# Misc.net
KiCad netlist of a schematic drawn in Altium Designer
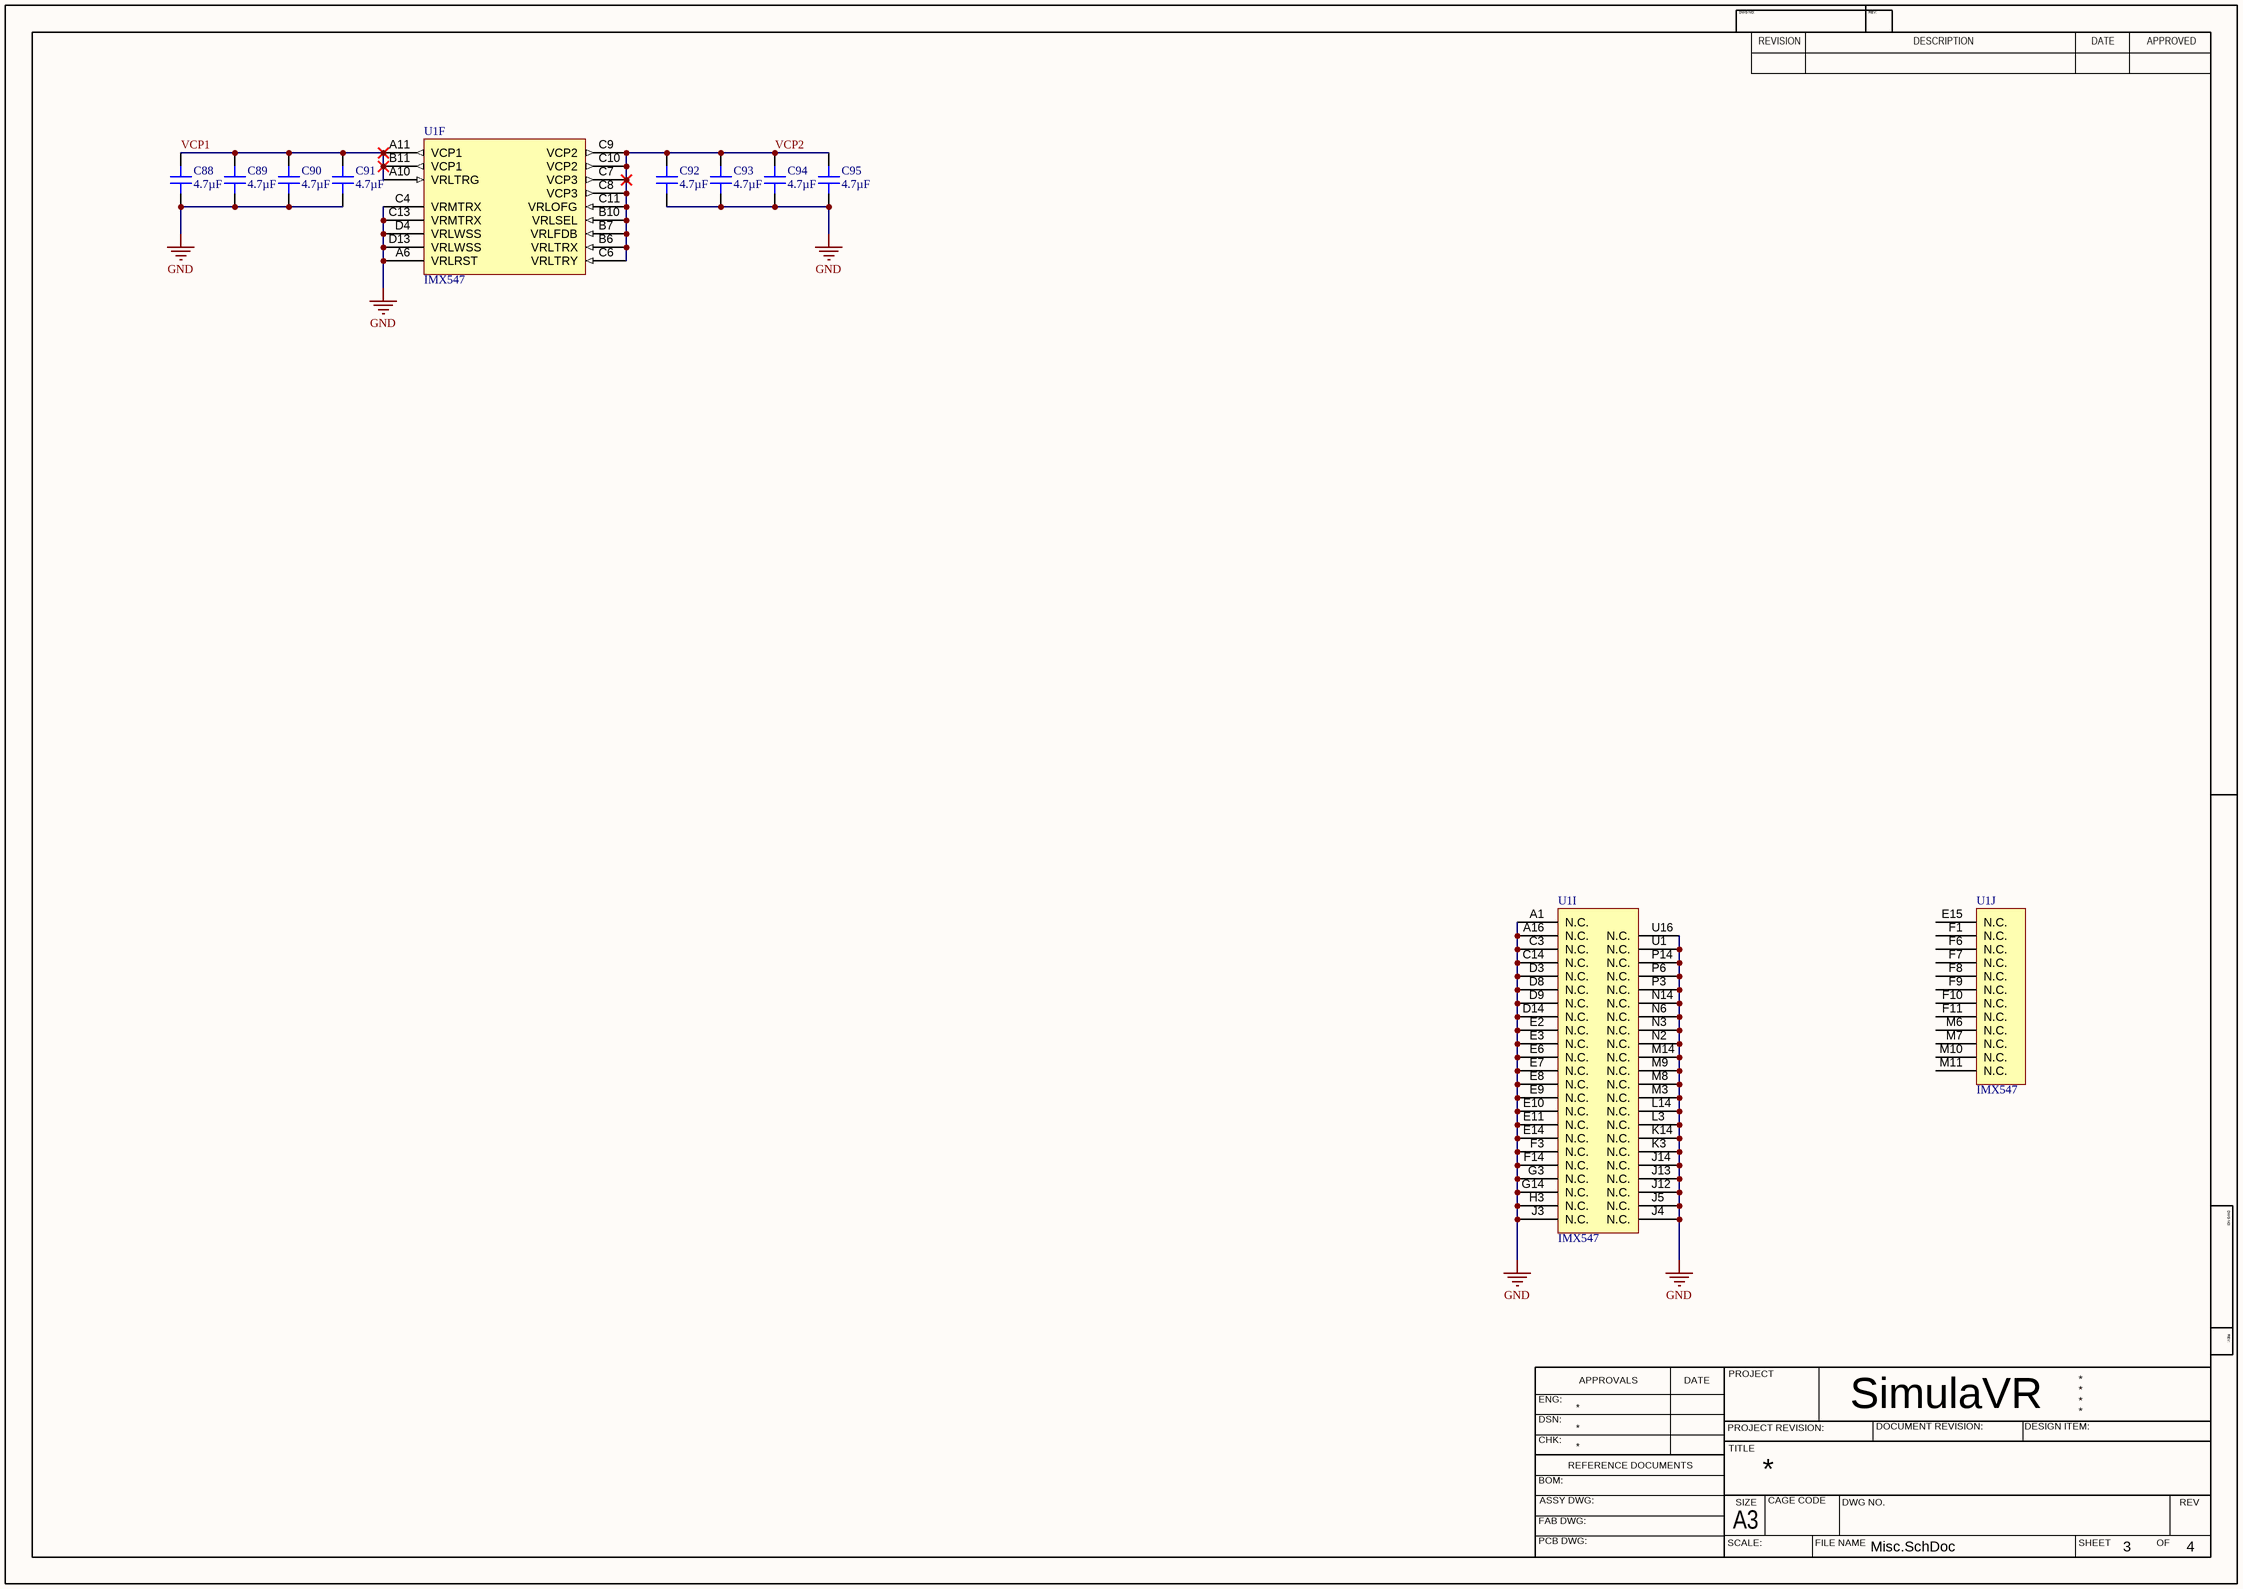
[diagram p0: Misc.SchDoc]

(export (version "E")
  (design (tool "Eeschema 10.0.6"))
  (components
    (comp (ref "C88")
      (value "4.7µF")
      (footprint "FP-GRM155-0_15-MFG")
      (description "CAP CER 4.7UF 10V X5R 0402")
      (fields
        (field (name "PART NUMBER") "GRM155R61A475MEAAD")
        (field (name "MANUFACTURER") "Murata Electronics")
      )
      (libsource (lib "Celestial Altium Library - altium_library") (part "Capacitor"))
    )
    (comp (ref "C89")
      (value "4.7µF")
      (footprint "FP-GRM155-0_15-MFG")
      (description "CAP CER 4.7UF 10V X5R 0402")
      (fields
        (field (name "PART NUMBER") "GRM155R61A475MEAAD")
        (field (name "MANUFACTURER") "Murata Electronics")
      )
      (libsource (lib "Celestial Altium Library - altium_library") (part "Capacitor"))
    )
    (comp (ref "C90")
      (value "4.7µF")
      (footprint "FP-GRM155-0_15-MFG")
      (description "CAP CER 4.7UF 10V X5R 0402")
      (fields
        (field (name "PART NUMBER") "GRM155R61A475MEAAD")
        (field (name "MANUFACTURER") "Murata Electronics")
      )
      (libsource (lib "Celestial Altium Library - altium_library") (part "Capacitor"))
    )
    (comp (ref "C91")
      (value "4.7µF")
      (footprint "FP-GRM155-0_15-MFG")
      (description "CAP CER 4.7UF 10V X5R 0402")
      (fields
        (field (name "PART NUMBER") "GRM155R61A475MEAAD")
        (field (name "MANUFACTURER") "Murata Electronics")
      )
      (libsource (lib "Celestial Altium Library - altium_library") (part "Capacitor"))
    )
    (comp (ref "C92")
      (value "4.7µF")
      (footprint "FP-GRM155-0_15-MFG")
      (description "CAP CER 4.7UF 10V X5R 0402")
      (fields
        (field (name "PART NUMBER") "GRM155R61A475MEAAD")
        (field (name "MANUFACTURER") "Murata Electronics")
      )
      (libsource (lib "Celestial Altium Library - altium_library") (part "Capacitor"))
    )
    (comp (ref "C93")
      (value "4.7µF")
      (footprint "FP-GRM155-0_15-MFG")
      (description "CAP CER 4.7UF 10V X5R 0402")
      (fields
        (field (name "PART NUMBER") "GRM155R61A475MEAAD")
        (field (name "MANUFACTURER") "Murata Electronics")
      )
      (libsource (lib "Celestial Altium Library - altium_library") (part "Capacitor"))
    )
    (comp (ref "C94")
      (value "4.7µF")
      (footprint "FP-GRM155-0_15-MFG")
      (description "CAP CER 4.7UF 10V X5R 0402")
      (fields
        (field (name "PART NUMBER") "GRM155R61A475MEAAD")
        (field (name "MANUFACTURER") "Murata Electronics")
      )
      (libsource (lib "Celestial Altium Library - altium_library") (part "Capacitor"))
    )
    (comp (ref "C95")
      (value "4.7µF")
      (footprint "FP-GRM155-0_15-MFG")
      (description "CAP CER 4.7UF 10V X5R 0402")
      (fields
        (field (name "PART NUMBER") "GRM155R61A475MEAAD")
        (field (name "MANUFACTURER") "Murata Electronics")
      )
      (libsource (lib "Celestial Altium Library - altium_library") (part "Capacitor"))
    )
    (comp (ref "U1")
      (value "IMX547")
      (footprint "LGA230C100P16X17_1680X2000X260")
      (description "Sony IMX547 sensor")
      (libsource (lib "David Kräutmann Beratung") (part "IMX547"))
    )
  )
  (nets
    (net (code "1") (name "/VCP1") (class "Default")
      (node (ref "C88") (pin "2") (pinfunction "2_2") (pintype "passive"))
      (node (ref "C89") (pin "2") (pinfunction "2_2") (pintype "passive"))
      (node (ref "C90") (pin "2") (pinfunction "2_2") (pintype "passive"))
      (node (ref "C91") (pin "2") (pinfunction "2_2") (pintype "passive"))
      (node (ref "U1") (pin "A10") (pinfunction "VRLTRG_A10") (pintype "input"))
      (node (ref "U1") (pin "A11") (pinfunction "VCP1_A11") (pintype "output"))
      (node (ref "U1") (pin "B11") (pinfunction "VCP1_B11") (pintype "output"))
    )
    (net (code "2") (name "/VCP2") (class "Default")
      (node (ref "C92") (pin "2") (pinfunction "2_2") (pintype "passive"))
      (node (ref "C93") (pin "2") (pinfunction "2_2") (pintype "passive"))
      (node (ref "C94") (pin "2") (pinfunction "2_2") (pintype "passive"))
      (node (ref "C95") (pin "2") (pinfunction "2_2") (pintype "passive"))
      (node (ref "U1") (pin "B10") (pinfunction "VRLSEL_B10") (pintype "input"))
      (node (ref "U1") (pin "B6") (pinfunction "VRLTRX_B6") (pintype "input"))
      (node (ref "U1") (pin "B7") (pinfunction "VRLFDB_B7") (pintype "input"))
      (node (ref "U1") (pin "C10") (pinfunction "VCP2_C10") (pintype "output"))
      (node (ref "U1") (pin "C11") (pinfunction "VRLOFG_C11") (pintype "input"))
      (node (ref "U1") (pin "C6") (pinfunction "VRLTRY_C6") (pintype "input"))
      (node (ref "U1") (pin "C7") (pinfunction "VCP3_C7") (pintype "output"))
      (node (ref "U1") (pin "C8") (pinfunction "VCP3_C8") (pintype "output"))
      (node (ref "U1") (pin "C9") (pinfunction "VCP2_C9") (pintype "output"))
    )
    (net (code "3") (name "GND") (class "Default")
      (node (ref "C88") (pin "1") (pinfunction "1_1") (pintype "passive"))
      (node (ref "C89") (pin "1") (pinfunction "1_1") (pintype "passive"))
      (node (ref "C90") (pin "1") (pinfunction "1_1") (pintype "passive"))
      (node (ref "C91") (pin "1") (pinfunction "1_1") (pintype "passive"))
      (node (ref "C92") (pin "1") (pinfunction "1_1") (pintype "passive"))
      (node (ref "C93") (pin "1") (pinfunction "1_1") (pintype "passive"))
      (node (ref "C94") (pin "1") (pinfunction "1_1") (pintype "passive"))
      (node (ref "C95") (pin "1") (pinfunction "1_1") (pintype "passive"))
      (node (ref "U1") (pin "A1") (pinfunction "N.C._A1") (pintype "passive"))
      (node (ref "U1") (pin "A16") (pinfunction "N.C._A16") (pintype "passive"))
      (node (ref "U1") (pin "A6") (pinfunction "VRLRST_A6") (pintype "power_in"))
      (node (ref "U1") (pin "C13") (pinfunction "VRMTRX_C13") (pintype "power_in"))
      (node (ref "U1") (pin "C14") (pinfunction "N.C._C14") (pintype "passive"))
      (node (ref "U1") (pin "C3") (pinfunction "N.C._C3") (pintype "passive"))
      (node (ref "U1") (pin "C4") (pinfunction "VRMTRX_C4") (pintype "power_in"))
      (node (ref "U1") (pin "D13") (pinfunction "VRLWSS_D13") (pintype "power_in"))
      (node (ref "U1") (pin "D14") (pinfunction "N.C._D14") (pintype "passive"))
      (node (ref "U1") (pin "D3") (pinfunction "N.C._D3") (pintype "passive"))
      (node (ref "U1") (pin "D4") (pinfunction "VRLWSS_D4") (pintype "power_in"))
      (node (ref "U1") (pin "D8") (pinfunction "N.C._D8") (pintype "passive"))
      (node (ref "U1") (pin "D9") (pinfunction "N.C._D9") (pintype "passive"))
      (node (ref "U1") (pin "E10") (pinfunction "N.C._E10") (pintype "passive"))
      (node (ref "U1") (pin "E11") (pinfunction "N.C._E11") (pintype "passive"))
      (node (ref "U1") (pin "E14") (pinfunction "N.C._E14") (pintype "passive"))
      (node (ref "U1") (pin "E2") (pinfunction "N.C._E2") (pintype "passive"))
      (node (ref "U1") (pin "E3") (pinfunction "N.C._E3") (pintype "passive"))
      (node (ref "U1") (pin "E6") (pinfunction "N.C._E6") (pintype "passive"))
      (node (ref "U1") (pin "E7") (pinfunction "N.C._E7") (pintype "passive"))
      (node (ref "U1") (pin "E8") (pinfunction "N.C._E8") (pintype "passive"))
      (node (ref "U1") (pin "E9") (pinfunction "N.C._E9") (pintype "passive"))
      (node (ref "U1") (pin "F14") (pinfunction "N.C._F14") (pintype "passive"))
      (node (ref "U1") (pin "F3") (pinfunction "N.C._F3") (pintype "passive"))
      (node (ref "U1") (pin "G14") (pinfunction "N.C._G14") (pintype "passive"))
      (node (ref "U1") (pin "G3") (pinfunction "N.C._G3") (pintype "passive"))
      (node (ref "U1") (pin "H3") (pinfunction "N.C._H3") (pintype "passive"))
      (node (ref "U1") (pin "J12") (pinfunction "N.C._J12") (pintype "passive"))
      (node (ref "U1") (pin "J13") (pinfunction "N.C._J13") (pintype "passive"))
      (node (ref "U1") (pin "J14") (pinfunction "N.C._J14") (pintype "passive"))
      (node (ref "U1") (pin "J3") (pinfunction "N.C._J3") (pintype "passive"))
      (node (ref "U1") (pin "J4") (pinfunction "N.C._J4") (pintype "passive"))
      (node (ref "U1") (pin "J5") (pinfunction "N.C._J5") (pintype "passive"))
      (node (ref "U1") (pin "K14") (pinfunction "N.C._K14") (pintype "passive"))
      (node (ref "U1") (pin "K3") (pinfunction "N.C._K3") (pintype "passive"))
      (node (ref "U1") (pin "L14") (pinfunction "N.C._L14") (pintype "passive"))
      (node (ref "U1") (pin "L3") (pinfunction "N.C._L3") (pintype "passive"))
      (node (ref "U1") (pin "M14") (pinfunction "N.C._M14") (pintype "passive"))
      (node (ref "U1") (pin "M3") (pinfunction "N.C._M3") (pintype "passive"))
      (node (ref "U1") (pin "M8") (pinfunction "N.C._M8") (pintype "passive"))
      (node (ref "U1") (pin "M9") (pinfunction "N.C._M9") (pintype "passive"))
      (node (ref "U1") (pin "N14") (pinfunction "N.C._N14") (pintype "passive"))
      (node (ref "U1") (pin "N2") (pinfunction "N.C._N2") (pintype "passive"))
      (node (ref "U1") (pin "N3") (pinfunction "N.C._N3") (pintype "passive"))
      (node (ref "U1") (pin "N6") (pinfunction "N.C._N6") (pintype "passive"))
      (node (ref "U1") (pin "P14") (pinfunction "N.C._P14") (pintype "passive"))
      (node (ref "U1") (pin "P3") (pinfunction "N.C._P3") (pintype "passive"))
      (node (ref "U1") (pin "P6") (pinfunction "N.C._P6") (pintype "passive"))
      (node (ref "U1") (pin "U1") (pinfunction "N.C._U1") (pintype "passive"))
      (node (ref "U1") (pin "U16") (pinfunction "N.C._U16") (pintype "passive"))
    )
    (net (code "4") (name "unconnected-(U1J-N.C.-PadE15)") (class "Default")
      (node (ref "U1") (pin "E15") (pinfunction "N.C._E15") (pintype "passive"))
    )
    (net (code "5") (name "unconnected-(U1J-N.C.-PadF1)") (class "Default")
      (node (ref "U1") (pin "F1") (pinfunction "N.C._F1") (pintype "passive"))
    )
    (net (code "6") (name "unconnected-(U1J-N.C.-PadF6)") (class "Default")
      (node (ref "U1") (pin "F6") (pinfunction "N.C._F6") (pintype "passive"))
    )
    (net (code "7") (name "unconnected-(U1J-N.C.-PadF7)") (class "Default")
      (node (ref "U1") (pin "F7") (pinfunction "N.C._F7") (pintype "passive"))
    )
    (net (code "8") (name "unconnected-(U1J-N.C.-PadF8)") (class "Default")
      (node (ref "U1") (pin "F8") (pinfunction "N.C._F8") (pintype "passive"))
    )
    (net (code "9") (name "unconnected-(U1J-N.C.-PadF9)") (class "Default")
      (node (ref "U1") (pin "F9") (pinfunction "N.C._F9") (pintype "passive"))
    )
    (net (code "10") (name "unconnected-(U1J-N.C.-PadF10)") (class "Default")
      (node (ref "U1") (pin "F10") (pinfunction "N.C._F10") (pintype "passive"))
    )
    (net (code "11") (name "unconnected-(U1J-N.C.-PadF11)") (class "Default")
      (node (ref "U1") (pin "F11") (pinfunction "N.C._F11") (pintype "passive"))
    )
    (net (code "12") (name "unconnected-(U1J-N.C.-PadM6)") (class "Default")
      (node (ref "U1") (pin "M6") (pinfunction "N.C._M6") (pintype "passive"))
    )
    (net (code "13") (name "unconnected-(U1J-N.C.-PadM7)") (class "Default")
      (node (ref "U1") (pin "M7") (pinfunction "N.C._M7") (pintype "passive"))
    )
    (net (code "14") (name "unconnected-(U1J-N.C.-PadM10)") (class "Default")
      (node (ref "U1") (pin "M10") (pinfunction "N.C._M10") (pintype "passive"))
    )
    (net (code "15") (name "unconnected-(U1J-N.C.-PadM11)") (class "Default")
      (node (ref "U1") (pin "M11") (pinfunction "N.C._M11") (pintype "passive"))
    )
  )
)
